# Power_Supply.net
KiCad netlist of a schematic drawn in Altium Designer
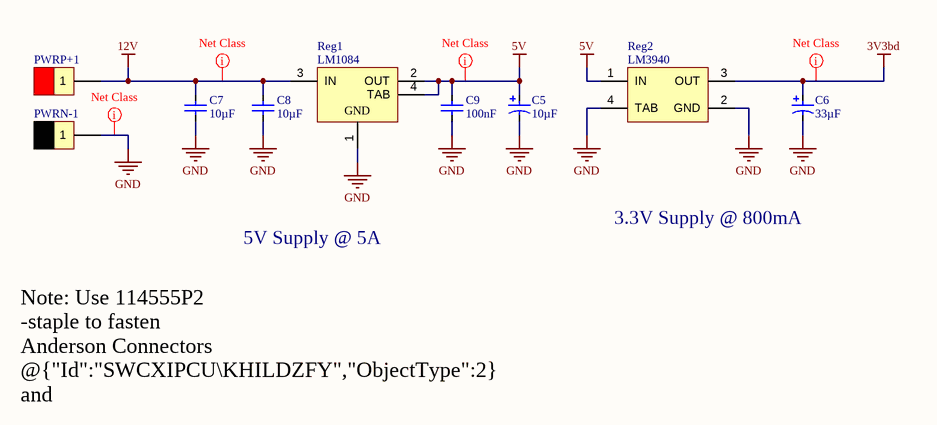
[diagram p0: Power Supply.SchDoc]

(export (version "E")
  (design (tool "Eeschema 10.0.6"))
  (components
    (comp (ref "C5")
      (value "10µF")
      (footprint "AVX-TPSB106K020R1000_L")
      (fields (field (name "Comment") "TPSB106K020R1000"))
      (libsource (lib "Advanced] Training Course - A365") (part "CAP_Polar Generic"))
    )
    (comp (ref "C6")
      (value "33µF")
      (footprint "FP-TAJY-MFG")
      (fields (field (name "Comment") "TAJY336K020RNJ"))
      (libsource (lib "Advanced] Training Course - A365") (part "CAP_Polar Generic"))
    )
    (comp (ref "C7")
      (value "10µF")
      (footprint "CAPC2013X135X45ML10T25")
      (fields (field (name "TOLERANCE") "10%") (field (name "Comment") "CAP_Murata"))
      (libsource (lib "Advanced] Training Course - A365") (part "CAP_Murata"))
    )
    (comp (ref "C8")
      (value "10µF")
      (footprint "CAPC2013X135X45ML10T25")
      (fields (field (name "TOLERANCE") "10%") (field (name "Comment") "CAP_Murata"))
      (libsource (lib "Advanced] Training Course - A365") (part "CAP_Murata"))
    )
    (comp (ref "C9")
      (value "100nF")
      (footprint "0603C_L")
      (fields (field (name "Comment") "Cap100nF_50V_0603"))
      (libsource (lib "Advanced] Training Course - A365") (part "CAP General"))
    )
    (comp (ref "PWRN-1")
      (value "Anderson-1Pin BLK_PCB_RHT")
      (footprint "Anderson_BLK_RHT_BOT")
      (description "Connector Accessory, Contact, Copper Alloy")
      (libsource (lib "Advanced] Training Course - A365") (part "Anderson-1Pin BLK_PCB_RHT"))
    )
    (comp (ref "PWRP+1")
      (value "Anderson-1Pin RED_PCB_RHT")
      (footprint "Anderson_RED_RHT_BOT")
      (description "Connector Accessory, Contact, Copper Alloy")
      (libsource (lib "TC - Altium Essentials Course A365 13") (part "Anderson-1Pin RED_PCB_RHT"))
    )
    (comp (ref "Reg1")
      (value "LM1084")
      (footprint "KTT0003B_L")
      (description "5A Low Dropout Positive Regulators, 3-pin TO-263, Pb-Free")
      (fields
        (field (name "MANUFACTURER") "Texas Instruments")
        (field (name "PARTNUMBER") "LM1084IS-5.0/NOPB")
        (field (name "SOURCE") "WCT.SchLib")
        (field (name "AVAILABLE PREVIEW IMAGES") "2D")
      )
      (libsource (lib "Advanced] Training Course - A365") (part "LM1084"))
    )
    (comp (ref "Reg2")
      (value "LM3940")
      (footprint "SOT223")
      (description "1A Low Dropout Regulator for 5V to 3.3V Conversion, 4-pin SOT-223, Pb-Free")
      (fields
        (field (name "MANUFACTURER") "Texas Instruments")
        (field (name "MANUFACTURER PART NUMBER") "LM3940IMP-3.3/NOPB")
        (field (name "SOURCE") "WCT.SchLib")
      )
      (libsource (lib "Advanced] Training Course - A365") (part "LM3940"))
    )
  )
  (nets
    (net (code "1") (name "3V3bd") (class "Default")
      (node (ref "C6") (pin "2") (pinfunction "2_2") (pintype "passive"))
      (node (ref "Reg2") (pin "3") (pinfunction "OUT_3") (pintype "power_in"))
    )
    (net (code "2") (name "5V") (class "Default")
      (node (ref "C5") (pin "2") (pinfunction "2_2") (pintype "passive"))
      (node (ref "C9") (pin "2") (pinfunction "2_2") (pintype "passive"))
      (node (ref "Reg1") (pin "2") (pinfunction "OUT_2") (pintype "power_in"))
      (node (ref "Reg1") (pin "4") (pinfunction "TAB_4") (pintype "power_in"))
      (node (ref "Reg2") (pin "1") (pinfunction "IN_1") (pintype "power_in"))
    )
    (net (code "3") (name "12V") (class "Default")
      (node (ref "C7") (pin "2") (pinfunction "2_2") (pintype "passive"))
      (node (ref "C8") (pin "2") (pinfunction "2_2") (pintype "passive"))
      (node (ref "PWRP+1") (pin "1") (pinfunction "1_1") (pintype "passive"))
      (node (ref "Reg1") (pin "3") (pinfunction "IN_3") (pintype "power_in"))
    )
    (net (code "4") (name "GND") (class "Default")
      (node (ref "C5") (pin "1") (pinfunction "1_1") (pintype "passive"))
      (node (ref "C6") (pin "1") (pinfunction "1_1") (pintype "passive"))
      (node (ref "C7") (pin "1") (pinfunction "1_1") (pintype "passive"))
      (node (ref "C8") (pin "1") (pinfunction "1_1") (pintype "passive"))
      (node (ref "C9") (pin "1") (pinfunction "1_1") (pintype "passive"))
      (node (ref "PWRN-1") (pin "1") (pinfunction "1_1") (pintype "passive"))
      (node (ref "Reg1") (pin "1") (pinfunction "GND_1") (pintype "power_in"))
      (node (ref "Reg2") (pin "2") (pinfunction "GND_2") (pintype "power_in"))
      (node (ref "Reg2") (pin "4") (pinfunction "TAB_4") (pintype "power_in"))
    )
  )
)
